# Sheet_1_2023-05-31.net
KiCad netlist of a schematic drawn in Altium Designer
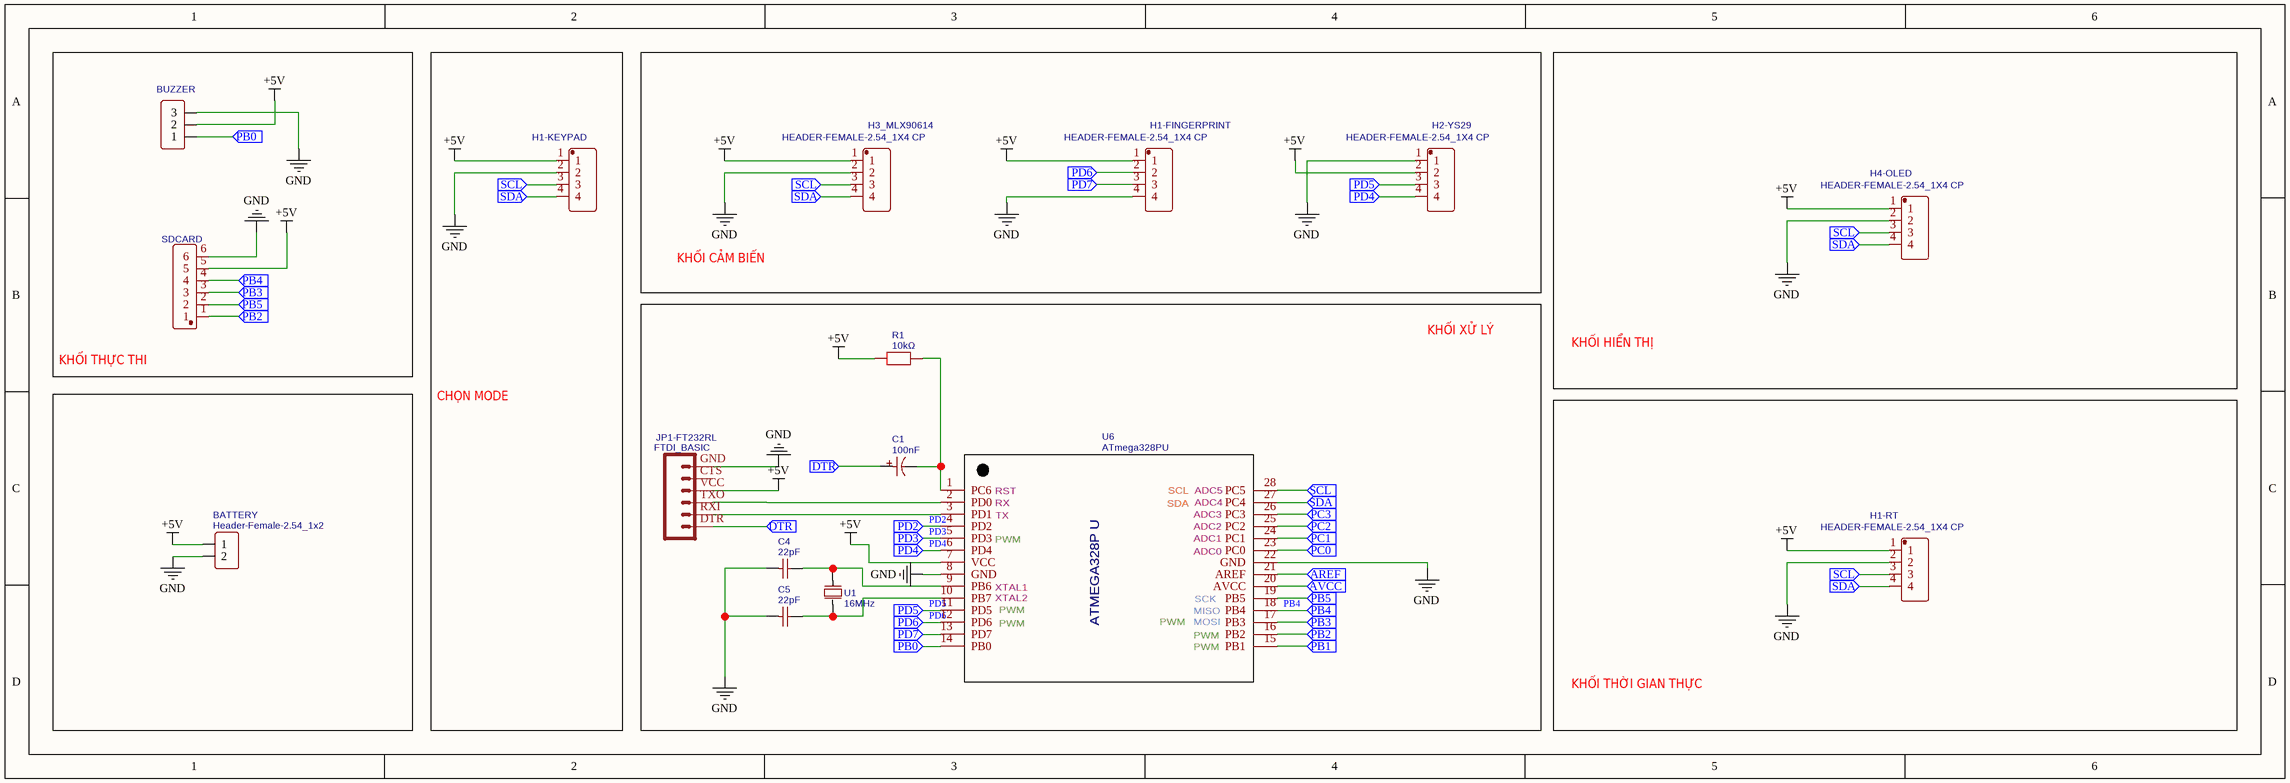
[diagram p0: Sheet_1_2023-05-31.schdoc]

(export (version "E")
  (design (tool "Eeschema 10.0.6"))
  (components
    (comp (ref "BATTERY")
      (value "Header-Female-2.54_1x2")
      (fields (field (name "BOM_MANUFACTURER PART") "2.54-1*2P母") (field (name "BOM_SUPPLIER PART") "C49661"))
      (libsource (lib "altium-import") (part "root_0_Header-Female-2.54_1x2_"))
    )
    (comp (ref "BUZZER")
      (value "Header-Female-2.54_1x3")
      (fields
        (field (name "BOM_SUPPLIER PART") "C146243")
        (field (name "BOM_MANUFACTURER PART") "2.54-1*3P母")
      )
      (libsource (lib "altium-import") (part "root_2_Header-Female-2.54_1x3_"))
    )
    (comp (ref "C1")
      (value "100nF")
      (fields
        (field (name "BOM_MANUFACTURER PART") "0.1uF 50V 5*11")
        (field (name "BOM_SUPPLIER PART") "C45091")
      )
      (libsource (lib "altium-import") (part "root_1_100nF_"))
    )
    (comp (ref "C4")
      (value "22pF")
      (fields
        (field (name "BOM_MANUFACTURER PART") "CC4-0805N220 J500")
        (field (name "BOM_SUPPLIER PART") "C3781")
      )
      (libsource (lib "altium-import") (part "root_0_22pF_"))
    )
    (comp (ref "C5")
      (value "22pF")
      (fields
        (field (name "BOM_MANUFACTURER PART") "CC4-0805N220 J500")
        (field (name "BOM_SUPPLIER PART") "C3781")
      )
      (libsource (lib "altium-import") (part "root_0_22pF_"))
    )
    (comp (ref "H1-FINGERPRINT")
      (value "HEADER-FEMALE-2.54_1X4 CP")
      (fields (field (name "CONTRIBUTOR") "chrisrisse"))
      (libsource (lib "altium-import") (part "root_0_HEADER-FEMALE-2.54_1X4 CP_"))
    )
    (comp (ref "H1-KEYPAD")
      (value "HEADER-FEMALE-2.54_1X4 CP")
      (fields (field (name "CONTRIBUTOR") "chrisrisse"))
      (libsource (lib "altium-import") (part "root_0_HEADER-FEMALE-2.54_1X4 CP_"))
    )
    (comp (ref "H1-RT")
      (value "HEADER-FEMALE-2.54_1X4 CP")
      (fields (field (name "CONTRIBUTOR") "chrisrisse"))
      (libsource (lib "altium-import") (part "root_0_HEADER-FEMALE-2.54_1X4 CP_"))
    )
    (comp (ref "H2-YS29")
      (value "HEADER-FEMALE-2.54_1X4 CP")
      (fields (field (name "CONTRIBUTOR") "chrisrisse"))
      (libsource (lib "altium-import") (part "root_0_HEADER-FEMALE-2.54_1X4 CP_"))
    )
    (comp (ref "H3_MLX90614")
      (value "HEADER-FEMALE-2.54_1X4 CP")
      (fields (field (name "CONTRIBUTOR") "chrisrisse"))
      (libsource (lib "altium-import") (part "root_0_HEADER-FEMALE-2.54_1X4 CP_"))
    )
    (comp (ref "H4-OLED")
      (value "HEADER-FEMALE-2.54_1X4 CP")
      (fields (field (name "CONTRIBUTOR") "chrisrisse"))
      (libsource (lib "altium-import") (part "root_0_HEADER-FEMALE-2.54_1X4 CP_"))
    )
    (comp (ref "JP1-FT232RL")
      (value "FTDI_BASIC")
      (fields (field (name "BOM_MANUFACTURER PART") "?") (field (name "CONTRIBUTOR") "SparkFun"))
      (libsource (lib "altium-import") (part "root_0_FTDI_BASIC_"))
    )
    (comp (ref "R1")
      (value "10kΩ")
      (fields
        (field (name "BOM_SUPPLIER PART") "C714145")
        (field (name "BOM_MANUFACTURER PART") "MF2WS-10KΩ±1%T")
        (field (name "CONTRIBUTOR") "LCSC")
      )
      (libsource (lib "altium-import") (part "root_0_10kΩ_"))
    )
    (comp (ref "SDCARD")
      (value "Header-Female-2.54_1x6")
      (fields (field (name "BOM_MANUFACTURER PART") "2.54-1*6P母") (field (name "BOM_SUPPLIER PART") "C40877"))
      (libsource (lib "altium-import") (part "root_2_Header-Female-2.54_1x6_"))
    )
    (comp (ref "U1")
      (value "16MHz")
      (fields
        (field (name "BOM_SUPPLIER PART") "C1669778")
        (field (name "BOM_MANUFACTURER PART") "MP160B")
        (field (name "CONTRIBUTOR") "lcsc")
      )
      (libsource (lib "altium-import") (part "root_1_16MHz_"))
    )
    (comp (ref "U6")
      (value "ATmega328PU")
      (fields
        (field (name "BOM_SUPPLIER PART") "E46335")
        (field (name "BOM_MANUFACTURER PART") "328PU")
        (field (name "CONTRIBUTOR") "jakub.mat977")
      )
      (libsource (lib "altium-import") (part "root_0_ATmega328PU_"))
    )
  )
  (nets
    (net (code "1") (name "+5V") (class "Default")
      (node (ref "BATTERY") (pin "1") (pinfunction "1_1") (pintype "passive"))
      (node (ref "BUZZER") (pin "2") (pinfunction "2_2") (pintype "passive"))
      (node (ref "H1-FINGERPRINT") (pin "1") (pinfunction "1_1") (pintype "passive"))
      (node (ref "H1-KEYPAD") (pin "1") (pinfunction "1_1") (pintype "passive"))
      (node (ref "H1-RT") (pin "1") (pinfunction "1_1") (pintype "passive"))
      (node (ref "H2-YS29") (pin "2") (pinfunction "2_2") (pintype "passive"))
      (node (ref "H3_MLX90614") (pin "1") (pinfunction "1_1") (pintype "passive"))
      (node (ref "H4-OLED") (pin "1") (pinfunction "1_1") (pintype "passive"))
      (node (ref "JP1-FT232RL") (pin "VCC") (pinfunction "4_VCC") (pintype "passive"))
      (node (ref "R1") (pin "1") (pinfunction "1_1") (pintype "passive"))
      (node (ref "SDCARD") (pin "5") (pinfunction "5_5") (pintype "passive"))
      (node (ref "U6") (pin "7") (pinfunction "VCC_7") (pintype "passive"))
    )
    (net (code "2") (name "/AREF") (class "Default")
      (node (ref "U6") (pin "21") (pinfunction "AREF_21") (pintype "passive"))
    )
    (net (code "3") (name "/AVCC") (class "Default")
      (node (ref "U6") (pin "20") (pinfunction "AVCC_20") (pintype "passive"))
    )
    (net (code "4") (name "/DTR") (class "Default")
      (node (ref "C1") (pin "1") (pinfunction "1_1") (pintype "passive"))
      (node (ref "JP1-FT232RL") (pin "DTR") (pinfunction "1_DTR") (pintype "passive"))
    )
    (net (code "5") (name "/PB0") (class "Default")
      (node (ref "BUZZER") (pin "1") (pinfunction "1_1") (pintype "passive"))
      (node (ref "U6") (pin "14") (pinfunction "PB0_14") (pintype "passive"))
    )
    (net (code "6") (name "/PB1") (class "Default")
      (node (ref "U6") (pin "15") (pinfunction "PB1_15") (pintype "passive"))
    )
    (net (code "7") (name "/PB2") (class "Default")
      (node (ref "SDCARD") (pin "1") (pinfunction "1_1") (pintype "passive"))
      (node (ref "U6") (pin "16") (pinfunction "PB2_16") (pintype "passive"))
    )
    (net (code "8") (name "/PB3") (class "Default")
      (node (ref "SDCARD") (pin "3") (pinfunction "3_3") (pintype "passive"))
      (node (ref "U6") (pin "17") (pinfunction "PB3_17") (pintype "passive"))
    )
    (net (code "9") (name "/PB4") (class "Default")
      (node (ref "SDCARD") (pin "4") (pinfunction "4_4") (pintype "passive"))
      (node (ref "U6") (pin "18") (pinfunction "PB4_18") (pintype "passive"))
    )
    (net (code "10") (name "/PB5") (class "Default")
      (node (ref "SDCARD") (pin "2") (pinfunction "2_2") (pintype "passive"))
      (node (ref "U6") (pin "19") (pinfunction "PB5_19") (pintype "passive"))
    )
    (net (code "11") (name "/PC0") (class "Default")
      (node (ref "U6") (pin "23") (pinfunction "PC0_23") (pintype "passive"))
    )
    (net (code "12") (name "/PC1") (class "Default")
      (node (ref "U6") (pin "24") (pinfunction "PC1_24") (pintype "passive"))
    )
    (net (code "13") (name "/PC2") (class "Default")
      (node (ref "U6") (pin "25") (pinfunction "PC2_25") (pintype "passive"))
    )
    (net (code "14") (name "/PC3") (class "Default")
      (node (ref "U6") (pin "26") (pinfunction "PC3_26") (pintype "passive"))
    )
    (net (code "15") (name "/PD2") (class "Default")
      (node (ref "U6") (pin "4") (pinfunction "PD2_4") (pintype "passive"))
    )
    (net (code "16") (name "/PD3") (class "Default")
      (node (ref "U6") (pin "5") (pinfunction "PD3_5") (pintype "passive"))
    )
    (net (code "17") (name "/PD4") (class "Default")
      (node (ref "H2-YS29") (pin "4") (pinfunction "4_4") (pintype "passive"))
      (node (ref "U6") (pin "6") (pinfunction "PD4_6") (pintype "passive"))
    )
    (net (code "18") (name "/PD5") (class "Default")
      (node (ref "H2-YS29") (pin "3") (pinfunction "3_3") (pintype "passive"))
      (node (ref "U6") (pin "11") (pinfunction "PD5_11") (pintype "passive"))
    )
    (net (code "19") (name "/PD6") (class "Default")
      (node (ref "H1-FINGERPRINT") (pin "2") (pinfunction "2_2") (pintype "passive"))
      (node (ref "U6") (pin "12") (pinfunction "PD6_12") (pintype "passive"))
    )
    (net (code "20") (name "/PD7") (class "Default")
      (node (ref "H1-FINGERPRINT") (pin "3") (pinfunction "3_3") (pintype "passive"))
      (node (ref "U6") (pin "13") (pinfunction "PD7_13") (pintype "passive"))
    )
    (net (code "21") (name "/SCL") (class "Default")
      (node (ref "H1-KEYPAD") (pin "3") (pinfunction "3_3") (pintype "passive"))
      (node (ref "H1-RT") (pin "3") (pinfunction "3_3") (pintype "passive"))
      (node (ref "H3_MLX90614") (pin "3") (pinfunction "3_3") (pintype "passive"))
      (node (ref "H4-OLED") (pin "3") (pinfunction "3_3") (pintype "passive"))
      (node (ref "U6") (pin "28") (pinfunction "PC5_28") (pintype "passive"))
    )
    (net (code "22") (name "/SDA") (class "Default")
      (node (ref "H1-KEYPAD") (pin "4") (pinfunction "4_4") (pintype "passive"))
      (node (ref "H1-RT") (pin "4") (pinfunction "4_4") (pintype "passive"))
      (node (ref "H3_MLX90614") (pin "4") (pinfunction "4_4") (pintype "passive"))
      (node (ref "H4-OLED") (pin "4") (pinfunction "4_4") (pintype "passive"))
      (node (ref "U6") (pin "27") (pinfunction "PC4_27") (pintype "passive"))
    )
    (net (code "23") (name "GND") (class "Default")
      (node (ref "BATTERY") (pin "2") (pinfunction "2_2") (pintype "passive"))
      (node (ref "BUZZER") (pin "3") (pinfunction "3_3") (pintype "passive"))
      (node (ref "C4") (pin "1") (pinfunction "1_1") (pintype "passive"))
      (node (ref "C5") (pin "1") (pinfunction "1_1") (pintype "passive"))
      (node (ref "H1-FINGERPRINT") (pin "4") (pinfunction "4_4") (pintype "passive"))
      (node (ref "H1-KEYPAD") (pin "2") (pinfunction "2_2") (pintype "passive"))
      (node (ref "H1-RT") (pin "2") (pinfunction "2_2") (pintype "passive"))
      (node (ref "H2-YS29") (pin "1") (pinfunction "1_1") (pintype "passive"))
      (node (ref "H3_MLX90614") (pin "2") (pinfunction "2_2") (pintype "passive"))
      (node (ref "H4-OLED") (pin "2") (pinfunction "2_2") (pintype "passive"))
      (node (ref "JP1-FT232RL") (pin "GND") (pinfunction "6_GND") (pintype "passive"))
      (node (ref "SDCARD") (pin "6") (pinfunction "6_6") (pintype "passive"))
      (node (ref "U6") (pin "22") (pinfunction "GND_22") (pintype "passive"))
      (node (ref "U6") (pin "8") (pinfunction "GND_8") (pintype "passive"))
    )
    (net (code "24") (name "Net-(JP1-FT232RL-2)") (class "Default")
      (node (ref "JP1-FT232RL") (pin "RXI") (pinfunction "2_RXI") (pintype "passive"))
      (node (ref "U6") (pin "3") (pinfunction "PD1_3") (pintype "passive"))
    )
    (net (code "25") (name "Net-(JP1-FT232RL-3)") (class "Default")
      (node (ref "JP1-FT232RL") (pin "TXO") (pinfunction "3_TXO") (pintype "passive"))
      (node (ref "U6") (pin "2") (pinfunction "PD0_2") (pintype "passive"))
    )
    (net (code "26") (name "Net-(U6-PB6)") (class "Default")
      (node (ref "C4") (pin "2") (pinfunction "2_2") (pintype "passive"))
      (node (ref "U1") (pin "2") (pinfunction "2_2") (pintype "passive"))
      (node (ref "U6") (pin "9") (pinfunction "PB6_9") (pintype "passive"))
    )
    (net (code "27") (name "Net-(U6-PB7)") (class "Default")
      (node (ref "C5") (pin "2") (pinfunction "2_2") (pintype "passive"))
      (node (ref "U1") (pin "1") (pinfunction "1_1") (pintype "passive"))
      (node (ref "U6") (pin "10") (pinfunction "PB7_10") (pintype "passive"))
    )
    (net (code "28") (name "Net-(U6-PC6)") (class "Default")
      (node (ref "C1") (pin "2") (pinfunction "2_2") (pintype "passive"))
      (node (ref "R1") (pin "2") (pinfunction "2_2") (pintype "passive"))
      (node (ref "U6") (pin "1") (pinfunction "PC6_1") (pintype "passive"))
    )
    (net (code "29") (name "unconnected-(JP1-FT232RL-5-PadCTS)") (class "Default")
      (node (ref "JP1-FT232RL") (pin "CTS") (pinfunction "5_CTS") (pintype "passive"))
    )
  )
)
